# LPCB235_-_SPI_UART_-_GROUP_B.net
KiCad netlist of a schematic drawn in Altium Designer
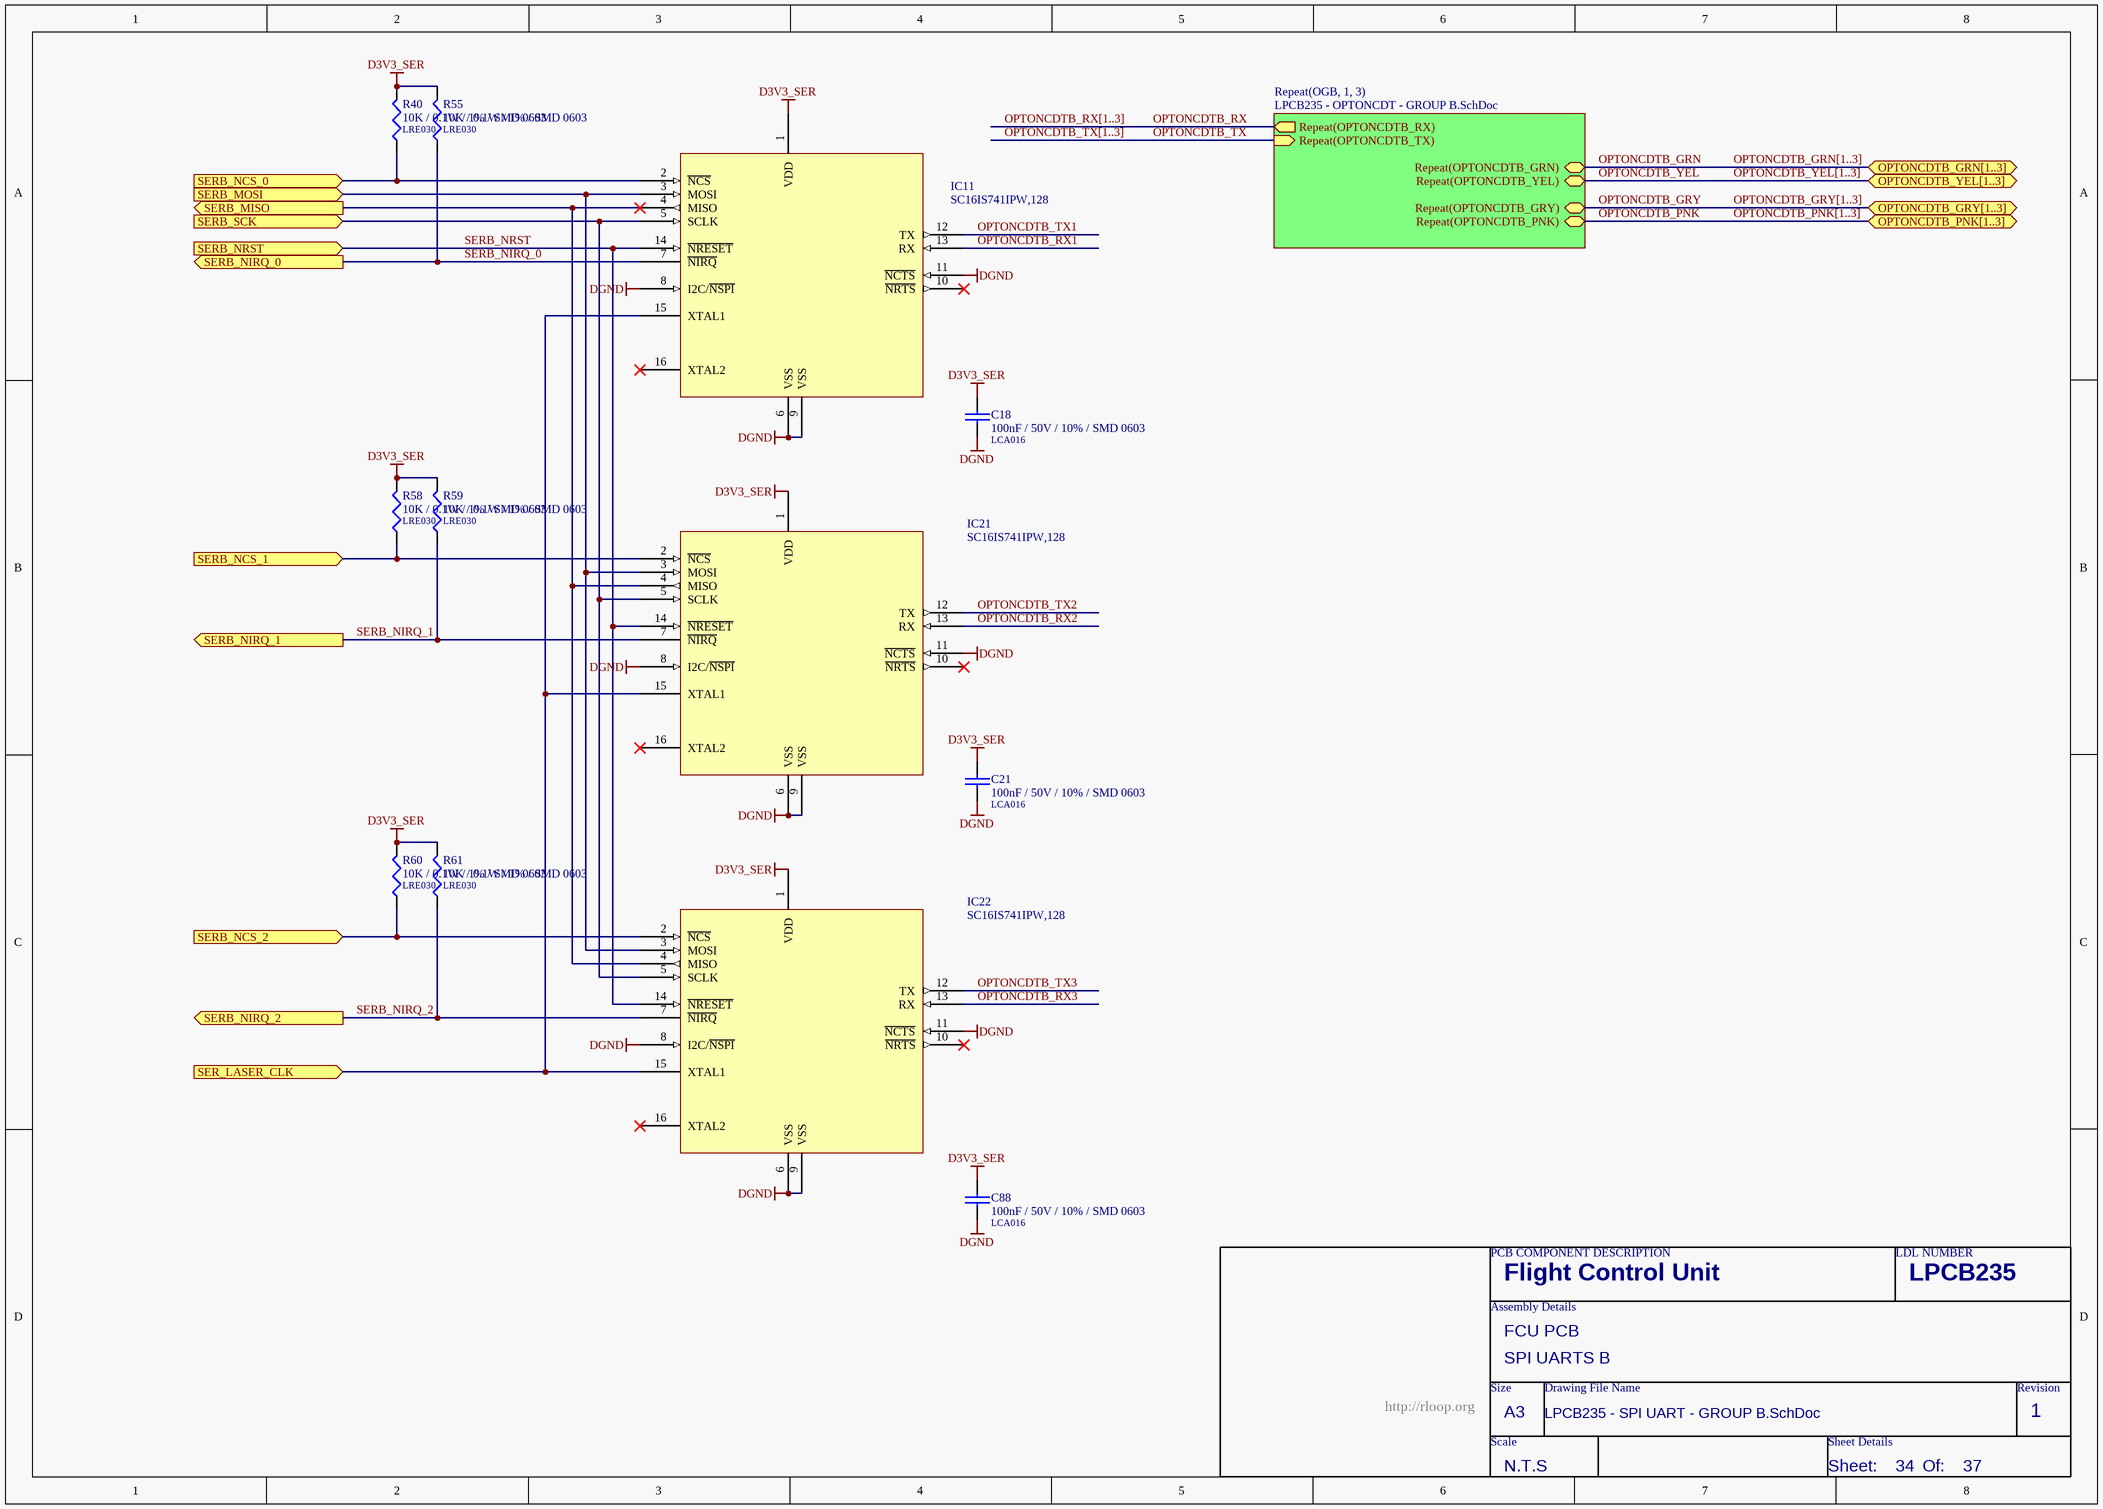
[diagram p0: LPCB235 - SPI UART - GROUP B.SchDoc]

(export (version "E")
  (design (tool "Eeschema 10.0.6"))
  (components
    (comp (ref "C18")
      (value "100nF / 50V / 10% / SMD 0603")
      (footprint "LFP011__CC1608-0603-IPC7351_B")
      (description "Capacitor, Ceramic Chip, 100nF (0.1uF), 50V, 5%, SMD 0603 [LCA016]")
      (fields (field (name "LDL_NUMBER") "LCA016"))
      (libsource (lib "LDL_Capacitors") (part "100nF / 50V / 10% / SMD 0603"))
    )
    (comp (ref "C21")
      (value "100nF / 50V / 10% / SMD 0603")
      (footprint "LFP011__CC1608-0603-IPC7351_B")
      (description "Capacitor, Ceramic Chip, 100nF (0.1uF), 50V, 5%, SMD 0603 [LCA016]")
      (fields (field (name "LDL_NUMBER") "LCA016"))
      (libsource (lib "LDL_Capacitors") (part "100nF / 50V / 10% / SMD 0603"))
    )
    (comp (ref "C88")
      (value "100nF / 50V / 10% / SMD 0603")
      (footprint "LFP011__CC1608-0603-IPC7351_B")
      (description "Capacitor, Ceramic Chip, 100nF (0.1uF), 50V, 5%, SMD 0603 [LCA016]")
      (fields (field (name "LDL_NUMBER") "LCA016"))
      (libsource (lib "LDL_Capacitors") (part "100nF / 50V / 10% / SMD 0603"))
    )
    (comp (ref "IC11")
      (value "SC16IS741IPW,128")
      (footprint "LFP049__TSSOP-16")
      (description "IC, SPI to UART bridge [LIC472]")
      (libsource (lib "LDL_Semiconductors") (part "SC16IS741IPW,128"))
    )
    (comp (ref "IC21")
      (value "SC16IS741IPW,128")
      (footprint "LFP049__TSSOP-16")
      (description "IC, SPI to UART bridge [LIC472]")
      (libsource (lib "LDL_Semiconductors") (part "SC16IS741IPW,128"))
    )
    (comp (ref "IC22")
      (value "SC16IS741IPW,128")
      (footprint "LFP049__TSSOP-16")
      (description "IC, SPI to UART bridge [LIC472]")
      (libsource (lib "LDL_Semiconductors") (part "SC16IS741IPW,128"))
    )
    (comp (ref "R40")
      (value "10K / 0.1W / 1% / SMD 0603")
      (footprint "LFP020__CR1608-0603-IPC7351_B")
      (description "Resistor, Ceramic Chip, 10K, 0.1W, 1%, SMD 0603 [LRE030]")
      (fields (field (name "LDL_NUMBER") "LRE030"))
      (libsource (lib "LDL_Resistors") (part "10K / 0.1W / 1% / SMD 0603"))
    )
    (comp (ref "R55")
      (value "10K / 0.1W / 1% / SMD 0603")
      (footprint "LFP020__CR1608-0603-IPC7351_B")
      (description "Resistor, Ceramic Chip, 10K, 0.1W, 1%, SMD 0603 [LRE030]")
      (fields (field (name "LDL_NUMBER") "LRE030"))
      (libsource (lib "LDL_Resistors") (part "10K / 0.1W / 1% / SMD 0603"))
    )
    (comp (ref "R58")
      (value "10K / 0.1W / 1% / SMD 0603")
      (footprint "LFP020__CR1608-0603-IPC7351_B")
      (description "Resistor, Ceramic Chip, 10K, 0.1W, 1%, SMD 0603 [LRE030]")
      (fields (field (name "LDL_NUMBER") "LRE030"))
      (libsource (lib "LDL_Resistors") (part "10K / 0.1W / 1% / SMD 0603"))
    )
    (comp (ref "R59")
      (value "10K / 0.1W / 1% / SMD 0603")
      (footprint "LFP020__CR1608-0603-IPC7351_B")
      (description "Resistor, Ceramic Chip, 10K, 0.1W, 1%, SMD 0603 [LRE030]")
      (fields (field (name "LDL_NUMBER") "LRE030"))
      (libsource (lib "LDL_Resistors") (part "10K / 0.1W / 1% / SMD 0603"))
    )
    (comp (ref "R60")
      (value "10K / 0.1W / 1% / SMD 0603")
      (footprint "LFP020__CR1608-0603-IPC7351_B")
      (description "Resistor, Ceramic Chip, 10K, 0.1W, 1%, SMD 0603 [LRE030]")
      (fields (field (name "LDL_NUMBER") "LRE030"))
      (libsource (lib "LDL_Resistors") (part "10K / 0.1W / 1% / SMD 0603"))
    )
    (comp (ref "R61")
      (value "10K / 0.1W / 1% / SMD 0603")
      (footprint "LFP020__CR1608-0603-IPC7351_B")
      (description "Resistor, Ceramic Chip, 10K, 0.1W, 1%, SMD 0603 [LRE030]")
      (fields (field (name "LDL_NUMBER") "LRE030"))
      (libsource (lib "LDL_Resistors") (part "10K / 0.1W / 1% / SMD 0603"))
    )
  )
  (nets
    (net (code "20") (name "/OPTONCDTB_RX1") (class "Default")
      (node (ref "IC11") (pin "13") (pinfunction "RX_13") (pintype "input"))
    )
    (net (code "21") (name "/OPTONCDTB_RX2") (class "Default")
      (node (ref "IC21") (pin "13") (pinfunction "RX_13") (pintype "input"))
    )
    (net (code "22") (name "/OPTONCDTB_RX3") (class "Default")
      (node (ref "IC22") (pin "13") (pinfunction "RX_13") (pintype "input"))
    )
    (net (code "25") (name "/OPTONCDTB_TX1") (class "Default")
      (node (ref "IC11") (pin "12") (pinfunction "TX_12") (pintype "output"))
    )
    (net (code "26") (name "/OPTONCDTB_TX2") (class "Default")
      (node (ref "IC21") (pin "12") (pinfunction "TX_12") (pintype "output"))
    )
    (net (code "27") (name "/OPTONCDTB_TX3") (class "Default")
      (node (ref "IC22") (pin "12") (pinfunction "TX_12") (pintype "output"))
    )
    (net (code "31") (name "/SERB_MISO") (class "Default")
      (node (ref "IC11") (pin "4") (pinfunction "MISO_4") (pintype "output"))
      (node (ref "IC21") (pin "4") (pinfunction "MISO_4") (pintype "output"))
      (node (ref "IC22") (pin "4") (pinfunction "MISO_4") (pintype "output"))
    )
    (net (code "32") (name "/SERB_MOSI") (class "Default")
      (node (ref "IC11") (pin "3") (pinfunction "MOSI_3") (pintype "input"))
      (node (ref "IC21") (pin "3") (pinfunction "MOSI_3") (pintype "input"))
      (node (ref "IC22") (pin "3") (pinfunction "MOSI_3") (pintype "input"))
    )
    (net (code "33") (name "/SERB_NCS_0") (class "Default")
      (node (ref "IC11") (pin "2") (pinfunction "~{NCS}_2") (pintype "input"))
      (node (ref "R40") (pin "1") (pintype "passive"))
    )
    (net (code "34") (name "/SERB_NCS_1") (class "Default")
      (node (ref "IC21") (pin "2") (pinfunction "~{NCS}_2") (pintype "input"))
      (node (ref "R58") (pin "1") (pintype "passive"))
    )
    (net (code "35") (name "/SERB_NCS_2") (class "Default")
      (node (ref "IC22") (pin "2") (pinfunction "~{NCS}_2") (pintype "input"))
      (node (ref "R60") (pin "1") (pintype "passive"))
    )
    (net (code "36") (name "/SERB_NIRQ_0") (class "Default")
      (node (ref "IC11") (pin "7") (pinfunction "~{NIRQ}_7") (pintype "passive"))
      (node (ref "R55") (pin "1") (pintype "passive"))
    )
    (net (code "37") (name "/SERB_NIRQ_1") (class "Default")
      (node (ref "IC21") (pin "7") (pinfunction "~{NIRQ}_7") (pintype "passive"))
      (node (ref "R59") (pin "1") (pintype "passive"))
    )
    (net (code "38") (name "/SERB_NIRQ_2") (class "Default")
      (node (ref "IC22") (pin "7") (pinfunction "~{NIRQ}_7") (pintype "passive"))
      (node (ref "R61") (pin "1") (pintype "passive"))
    )
    (net (code "39") (name "/SERB_NRST") (class "Default")
      (node (ref "IC11") (pin "14") (pinfunction "~{NRESET}_14") (pintype "input"))
      (node (ref "IC21") (pin "14") (pinfunction "~{NRESET}_14") (pintype "input"))
      (node (ref "IC22") (pin "14") (pinfunction "~{NRESET}_14") (pintype "input"))
    )
    (net (code "40") (name "/SERB_SCK") (class "Default")
      (node (ref "IC11") (pin "5") (pinfunction "SCLK_5") (pintype "input"))
      (node (ref "IC21") (pin "5") (pinfunction "SCLK_5") (pintype "input"))
      (node (ref "IC22") (pin "5") (pinfunction "SCLK_5") (pintype "input"))
    )
    (net (code "41") (name "/SER_LASER_CLK") (class "Default")
      (node (ref "IC11") (pin "15") (pinfunction "XTAL1_15") (pintype "passive"))
      (node (ref "IC21") (pin "15") (pinfunction "XTAL1_15") (pintype "passive"))
      (node (ref "IC22") (pin "15") (pinfunction "XTAL1_15") (pintype "passive"))
    )
    (net (code "42") (name "D3V3_SER") (class "Default")
      (node (ref "C18") (pin "1") (pintype "passive"))
      (node (ref "C21") (pin "1") (pintype "passive"))
      (node (ref "C88") (pin "1") (pintype "passive"))
      (node (ref "IC11") (pin "1") (pinfunction "VDD_1") (pintype "power_in"))
      (node (ref "IC21") (pin "1") (pinfunction "VDD_1") (pintype "power_in"))
      (node (ref "IC22") (pin "1") (pinfunction "VDD_1") (pintype "power_in"))
      (node (ref "R40") (pin "2") (pintype "passive"))
      (node (ref "R55") (pin "2") (pintype "passive"))
      (node (ref "R58") (pin "2") (pintype "passive"))
      (node (ref "R59") (pin "2") (pintype "passive"))
      (node (ref "R60") (pin "2") (pintype "passive"))
      (node (ref "R61") (pin "2") (pintype "passive"))
    )
    (net (code "43") (name "DGND") (class "Default")
      (node (ref "C18") (pin "2") (pintype "passive"))
      (node (ref "C21") (pin "2") (pintype "passive"))
      (node (ref "C88") (pin "2") (pintype "passive"))
      (node (ref "IC11") (pin "11") (pinfunction "~{NCTS}_11") (pintype "input"))
      (node (ref "IC11") (pin "6") (pinfunction "VSS_6") (pintype "power_in"))
      (node (ref "IC11") (pin "8") (pinfunction "I2C/~{NSPI}_8") (pintype "input"))
      (node (ref "IC11") (pin "9") (pinfunction "VSS_9") (pintype "power_in"))
      (node (ref "IC21") (pin "11") (pinfunction "~{NCTS}_11") (pintype "input"))
      (node (ref "IC21") (pin "6") (pinfunction "VSS_6") (pintype "power_in"))
      (node (ref "IC21") (pin "8") (pinfunction "I2C/~{NSPI}_8") (pintype "input"))
      (node (ref "IC21") (pin "9") (pinfunction "VSS_9") (pintype "power_in"))
      (node (ref "IC22") (pin "11") (pinfunction "~{NCTS}_11") (pintype "input"))
      (node (ref "IC22") (pin "6") (pinfunction "VSS_6") (pintype "power_in"))
      (node (ref "IC22") (pin "8") (pinfunction "I2C/~{NSPI}_8") (pintype "input"))
      (node (ref "IC22") (pin "9") (pinfunction "VSS_9") (pintype "power_in"))
    )
    (net (code "44") (name "unconnected-(IC11-XTAL2-Pad16)") (class "Default")
      (node (ref "IC11") (pin "16") (pinfunction "XTAL2_16") (pintype "passive+no_connect"))
    )
    (net (code "45") (name "unconnected-(IC11-~{NRTS}-Pad10)") (class "Default")
      (node (ref "IC11") (pin "10") (pinfunction "~{NRTS}_10") (pintype "output+no_connect"))
    )
    (net (code "46") (name "unconnected-(IC21-XTAL2-Pad16)") (class "Default")
      (node (ref "IC21") (pin "16") (pinfunction "XTAL2_16") (pintype "passive+no_connect"))
    )
    (net (code "47") (name "unconnected-(IC21-~{NRTS}-Pad10)") (class "Default")
      (node (ref "IC21") (pin "10") (pinfunction "~{NRTS}_10") (pintype "output+no_connect"))
    )
    (net (code "48") (name "unconnected-(IC22-XTAL2-Pad16)") (class "Default")
      (node (ref "IC22") (pin "16") (pinfunction "XTAL2_16") (pintype "passive+no_connect"))
    )
    (net (code "49") (name "unconnected-(IC22-~{NRTS}-Pad10)") (class "Default")
      (node (ref "IC22") (pin "10") (pinfunction "~{NRTS}_10") (pintype "output+no_connect"))
    )
  )
)
